# DRIVER_2.net
KiCad netlist of a schematic drawn in Altium Designer
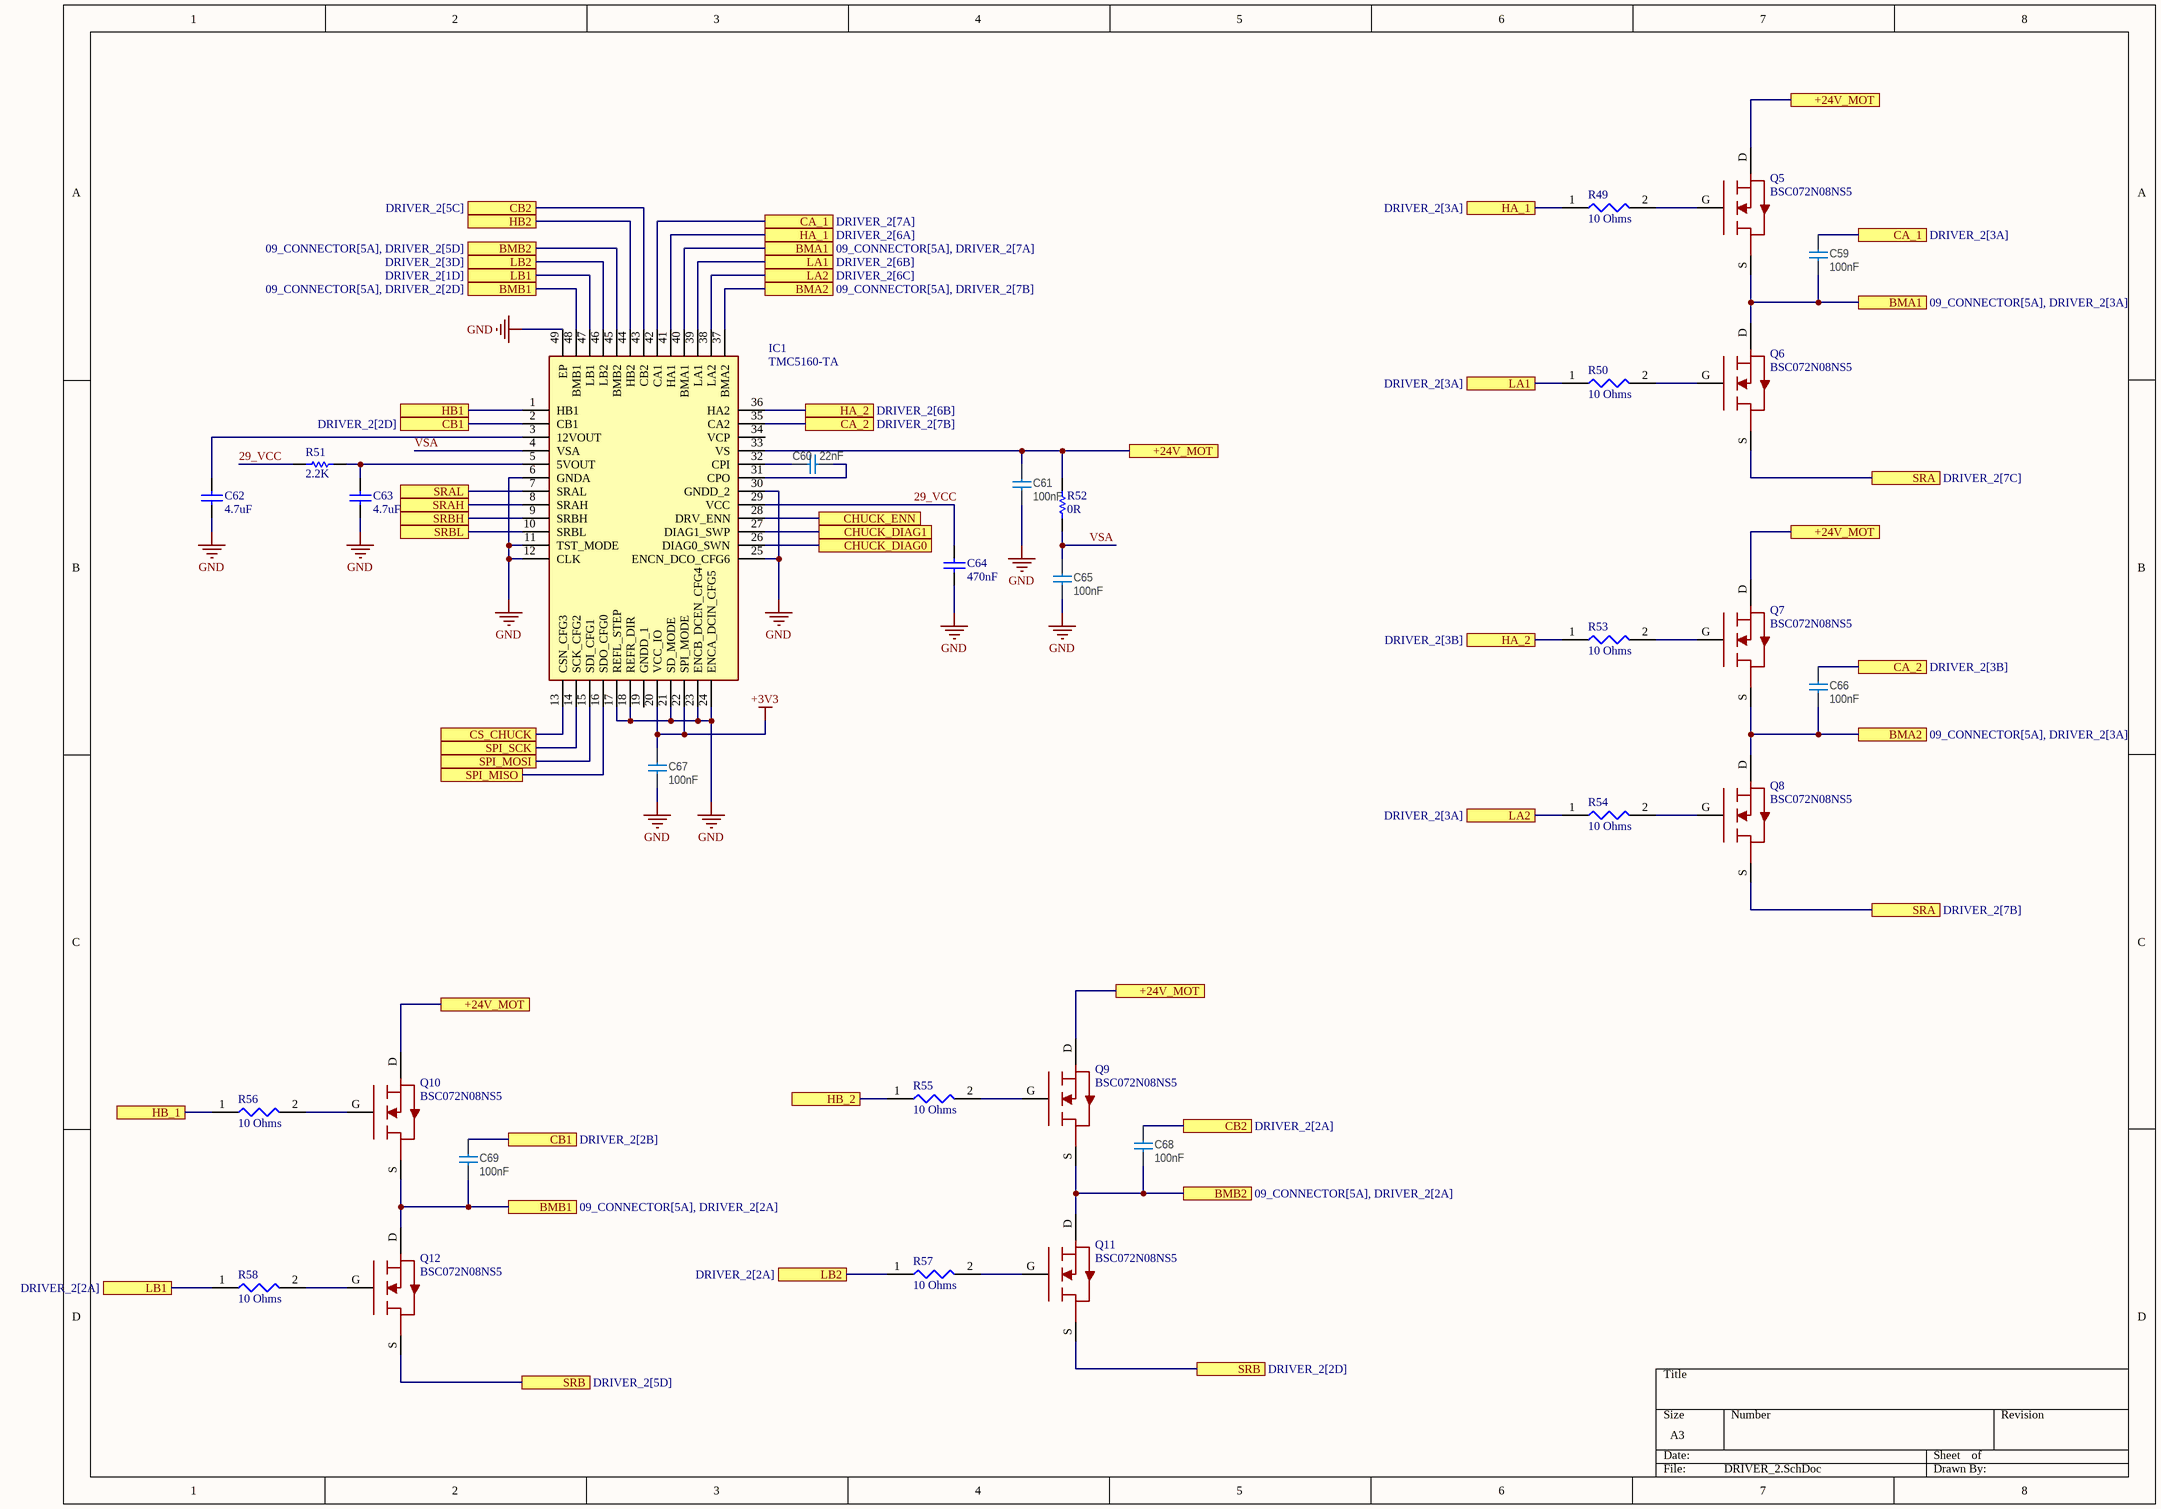
[diagram p0: DRIVER_2.SchDoc]

(export (version "E")
  (design (tool "Eeschema 10.0.6"))
  (components
    (comp (ref "C59")
      (value "100nF")
      (footprint "CAPC0603X03L_C")
      (description "Capacitor, X5R, ±10%")
      (fields
        (field (name "PART NUMBER") "C0201-100n")
        (field (name "MANUFACTURER") "N.A.")
        (field (name "AUTHOR") "rsk")
      )
      (libsource (lib "HW_ADHERENT_SYSCTRL_R1_L1") (part "C0201-100n"))
    )
    (comp (ref "C60")
      (value "22nF")
      (footprint "CAPC0603X03L_C")
      (description "Capacitor, Ceramic, 22nF 10V X5R 0201,±10%")
      (fields
        (field (name "PART NUMBER") "C0201-22n-10V-X5R-GRM033R61A223KE84")
        (field (name "MANUFACTURER") "Murata")
        (field (name "AUTHOR") "prbu")
      )
      (libsource (lib "HW_ADHERENT_SYSCTRL_R1_L1") (part "C0201-22n-10V-X5R-GRM033R61A223KE84_1"))
    )
    (comp (ref "C61")
      (value "100nF")
      (footprint "CAPC0603X03L_C")
      (description "Capacitor, X5R, ±10%")
      (fields
        (field (name "PART NUMBER") "C0201-100n")
        (field (name "MANUFACTURER") "N.A.")
        (field (name "AUTHOR") "rsk")
      )
      (libsource (lib "HW_ADHERENT_SYSCTRL_R1_L1") (part "C0201-100n"))
    )
    (comp (ref "C62")
      (value "4.7uF")
      (footprint "SMC0805")
      (description "4.7 µF ±10% 50V Ceramic Capacitor X5R 0805 (2012 Metric)")
      (fields
        (field (name "MANUFACTURER PART NUMBER") "GRT21BR61H475KE13L")
        (field (name "Comment") "CAP CER 4.7UF 50V X5R 0805")
      )
      (libsource (lib "HW_ADHERENT_SYSCTRL_R1_L2") (part "CAP0805_4.7UF_50V"))
    )
    (comp (ref "C63")
      (value "4.7uF")
      (footprint "SMC0805")
      (description "4.7 µF ±10% 50V Ceramic Capacitor X5R 0805 (2012 Metric)")
      (fields
        (field (name "MANUFACTURER PART NUMBER") "GRT21BR61H475KE13L")
        (field (name "Comment") "CAP CER 4.7UF 50V X5R 0805")
      )
      (libsource (lib "HW_ADHERENT_SYSCTRL_R1_L2") (part "CAP0805_4.7UF_50V"))
    )
    (comp (ref "C64")
      (value "470nF")
      (footprint "CAP0402(1005)x0.5")
      (description "0.47 µF ±10% 10V Ceramic Capacitor X5R 0402 (1005 Metric)")
      (fields
        (field (name "MANUFACTURER PART NUMBER") "CL05A474KP5NNNC")
        (field (name "LCSC PART NUMBER") "C47339")
      )
      (libsource (lib "HW_ADHERENT_SYSCTRL_R1_L2") (part "CAP0402_470NF_10V"))
    )
    (comp (ref "C65")
      (value "100nF")
      (footprint "CAPC0603X03L_C")
      (description "Capacitor, X5R, ±10%")
      (fields
        (field (name "PART NUMBER") "C0201-100n")
        (field (name "MANUFACTURER") "N.A.")
        (field (name "AUTHOR") "rsk")
      )
      (libsource (lib "HW_ADHERENT_SYSCTRL_R1_L1") (part "C0201-100n"))
    )
    (comp (ref "C66")
      (value "100nF")
      (footprint "CAPC0603X03L_C")
      (description "Capacitor, X5R, ±10%")
      (fields
        (field (name "PART NUMBER") "C0201-100n")
        (field (name "MANUFACTURER") "N.A.")
        (field (name "AUTHOR") "rsk")
      )
      (libsource (lib "HW_ADHERENT_SYSCTRL_R1_L1") (part "C0201-100n"))
    )
    (comp (ref "C67")
      (value "100nF")
      (footprint "CAPC0603X03L_C")
      (description "Capacitor, X5R, ±10%")
      (fields
        (field (name "PART NUMBER") "C0201-100n")
        (field (name "MANUFACTURER") "N.A.")
        (field (name "AUTHOR") "rsk")
      )
      (libsource (lib "HW_ADHERENT_SYSCTRL_R1_L1") (part "C0201-100n"))
    )
    (comp (ref "C68")
      (value "100nF")
      (footprint "CAPC0603X03L_C")
      (description "Capacitor, X5R, ±10%")
      (fields
        (field (name "PART NUMBER") "C0201-100n")
        (field (name "MANUFACTURER") "N.A.")
        (field (name "AUTHOR") "rsk")
      )
      (libsource (lib "HW_ADHERENT_SYSCTRL_R1_L1") (part "C0201-100n"))
    )
    (comp (ref "C69")
      (value "100nF")
      (footprint "CAPC0603X03L_C")
      (description "Capacitor, X5R, ±10%")
      (fields
        (field (name "PART NUMBER") "C0201-100n")
        (field (name "MANUFACTURER") "N.A.")
        (field (name "AUTHOR") "rsk")
      )
      (libsource (lib "HW_ADHERENT_SYSCTRL_R1_L1") (part "C0201-100n"))
    )
    (comp (ref "IC1")
      (value "TMC5160-TA")
      (footprint "SamacSys:QFP50P900X900X120-49N")
      (description "Integrated Circuit")
      (libsource (lib "*") (part "TMC5160-TA"))
    )
    (comp (ref "Q5")
      (value "BSC072N08NS5")
      (footprint "SamacSys:BSC080N03LSG")
      (description "Transistor")
      (libsource (lib "SamacSys") (part "BSC072N08NS5"))
    )
    (comp (ref "Q6")
      (value "BSC072N08NS5")
      (footprint "SamacSys:BSC080N03LSG")
      (description "Transistor")
      (libsource (lib "SamacSys") (part "BSC072N08NS5"))
    )
    (comp (ref "Q7")
      (value "BSC072N08NS5")
      (footprint "SamacSys:BSC080N03LSG")
      (description "Transistor")
      (libsource (lib "SamacSys") (part "BSC072N08NS5"))
    )
    (comp (ref "Q8")
      (value "BSC072N08NS5")
      (footprint "SamacSys:BSC080N03LSG")
      (description "Transistor")
      (libsource (lib "SamacSys") (part "BSC072N08NS5"))
    )
    (comp (ref "Q9")
      (value "BSC072N08NS5")
      (footprint "SamacSys:BSC080N03LSG")
      (description "Transistor")
      (libsource (lib "SamacSys") (part "BSC072N08NS5"))
    )
    (comp (ref "Q10")
      (value "BSC072N08NS5")
      (footprint "SamacSys:BSC080N03LSG")
      (description "Transistor")
      (libsource (lib "SamacSys") (part "BSC072N08NS5"))
    )
    (comp (ref "Q11")
      (value "BSC072N08NS5")
      (footprint "SamacSys:BSC080N03LSG")
      (description "Transistor")
      (libsource (lib "SamacSys") (part "BSC072N08NS5"))
    )
    (comp (ref "Q12")
      (value "BSC072N08NS5")
      (footprint "SamacSys:BSC080N03LSG")
      (description "Transistor")
      (libsource (lib "SamacSys") (part "BSC072N08NS5"))
    )
    (comp (ref "R49")
      (value "10 Ohms")
      (footprint "SamacSys:RESC1608X55N")
      (description "Resistor")
      (fields
        (field (name "MANUFACTURER_PART_NUMBER") "RNCF0603AKT10R0")
        (field (name "MOUSER PART NUMBER") "708-RNCF0603AKT10R0")
      )
      (libsource (lib "SamacSys") (part "RNCF0603AKT10R0"))
    )
    (comp (ref "R50")
      (value "10 Ohms")
      (footprint "SamacSys:RESC1608X55N")
      (description "Resistor")
      (fields
        (field (name "MANUFACTURER_PART_NUMBER") "RNCF0603AKT10R0")
        (field (name "MOUSER PART NUMBER") "708-RNCF0603AKT10R0")
      )
      (libsource (lib "SamacSys") (part "RNCF0603AKT10R0"))
    )
    (comp (ref "R51")
      (value "2.2K")
      (footprint "0402_R")
      (description "RES 2.2K OHM 1% 1/16W 0402")
      (fields
        (field (name "MANUFACTURER PART NUMBER") "RC0402FR-072K2L")
        (field (name "MANUFACTURER") "Yageo")
      )
      (libsource (lib "HW_ADHERENT_SYSCTRL_R1_L2") (part "Res1_7"))
    )
    (comp (ref "R52")
      (value "0R")
      (footprint "0402_R")
      (description "RES 0 OHM JUMPER 1/16W 0402")
      (fields
        (field (name "MANUFACTURER PART NUMBER") "RC0402FR-070RL")
        (field (name "MANUFACTURER") "Yageo")
      )
      (libsource (lib "HW_ADHERENT_SYSCTRL_R1_L2") (part "Res1"))
    )
    (comp (ref "R53")
      (value "10 Ohms")
      (footprint "SamacSys:RESC1608X55N")
      (description "Resistor")
      (fields
        (field (name "MANUFACTURER_PART_NUMBER") "RNCF0603AKT10R0")
        (field (name "MOUSER PART NUMBER") "708-RNCF0603AKT10R0")
      )
      (libsource (lib "SamacSys") (part "RNCF0603AKT10R0"))
    )
    (comp (ref "R54")
      (value "10 Ohms")
      (footprint "SamacSys:RESC1608X55N")
      (description "Resistor")
      (fields
        (field (name "MANUFACTURER_PART_NUMBER") "RNCF0603AKT10R0")
        (field (name "MOUSER PART NUMBER") "708-RNCF0603AKT10R0")
      )
      (libsource (lib "SamacSys") (part "RNCF0603AKT10R0"))
    )
    (comp (ref "R55")
      (value "10 Ohms")
      (footprint "SamacSys:RESC1608X55N")
      (description "Resistor")
      (fields
        (field (name "MANUFACTURER_PART_NUMBER") "RNCF0603AKT10R0")
        (field (name "MOUSER PART NUMBER") "708-RNCF0603AKT10R0")
      )
      (libsource (lib "SamacSys") (part "RNCF0603AKT10R0"))
    )
    (comp (ref "R56")
      (value "10 Ohms")
      (footprint "SamacSys:RESC1608X55N")
      (description "Resistor")
      (fields
        (field (name "MANUFACTURER_PART_NUMBER") "RNCF0603AKT10R0")
        (field (name "MOUSER PART NUMBER") "708-RNCF0603AKT10R0")
      )
      (libsource (lib "SamacSys") (part "RNCF0603AKT10R0"))
    )
    (comp (ref "R57")
      (value "10 Ohms")
      (footprint "SamacSys:RESC1608X55N")
      (description "Resistor")
      (fields
        (field (name "MANUFACTURER_PART_NUMBER") "RNCF0603AKT10R0")
        (field (name "MOUSER PART NUMBER") "708-RNCF0603AKT10R0")
      )
      (libsource (lib "SamacSys") (part "RNCF0603AKT10R0"))
    )
    (comp (ref "R58")
      (value "10 Ohms")
      (footprint "SamacSys:RESC1608X55N")
      (description "Resistor")
      (fields
        (field (name "MANUFACTURER_PART_NUMBER") "RNCF0603AKT10R0")
        (field (name "MOUSER PART NUMBER") "708-RNCF0603AKT10R0")
      )
      (libsource (lib "SamacSys") (part "RNCF0603AKT10R0"))
    )
  )
  (nets
    (net (code "1") (name "+3V3") (class "Default")
      (node (ref "C67") (pin "2") (pinfunction "2_2") (pintype "passive"))
      (node (ref "IC1") (pin "20") (pinfunction "VCC_IO_20") (pintype "passive"))
      (node (ref "IC1") (pin "22") (pinfunction "SPI_MODE_22") (pintype "passive"))
    )
    (net (code "2") (name "/+24V_MOT") (class "Default")
      (node (ref "C61") (pin "2") (pinfunction "2_2") (pintype "passive"))
      (node (ref "IC1") (pin "33") (pinfunction "VS_33") (pintype "passive"))
      (node (ref "Q10") (pin "D") (pinfunction "D_D") (pintype "passive"))
      (node (ref "Q5") (pin "D") (pinfunction "D_D") (pintype "passive"))
      (node (ref "Q7") (pin "D") (pinfunction "D_D") (pintype "passive"))
      (node (ref "Q9") (pin "D") (pinfunction "D_D") (pintype "passive"))
      (node (ref "R52") (pin "2") (pinfunction "2_2") (pintype "passive"))
    )
    (net (code "3") (name "/29_VCC") (class "Default")
      (node (ref "C64") (pin "2") (pinfunction "2_2") (pintype "passive"))
      (node (ref "IC1") (pin "29") (pinfunction "VCC_29") (pintype "passive"))
      (node (ref "R51") (pin "2") (pinfunction "2_2") (pintype "passive"))
    )
    (net (code "4") (name "/BMA1") (class "Default")
      (node (ref "C59") (pin "1") (pinfunction "1_1") (pintype "passive"))
      (node (ref "IC1") (pin "40") (pinfunction "BMA1_40") (pintype "passive"))
      (node (ref "Q5") (pin "S") (pinfunction "S_S") (pintype "passive"))
      (node (ref "Q6") (pin "D") (pinfunction "D_D") (pintype "passive"))
    )
    (net (code "5") (name "/BMA2") (class "Default")
      (node (ref "C66") (pin "1") (pinfunction "1_1") (pintype "passive"))
      (node (ref "IC1") (pin "37") (pinfunction "BMA2_37") (pintype "passive"))
      (node (ref "Q7") (pin "S") (pinfunction "S_S") (pintype "passive"))
      (node (ref "Q8") (pin "D") (pinfunction "D_D") (pintype "passive"))
    )
    (net (code "6") (name "/BMB1") (class "Default")
      (node (ref "C69") (pin "1") (pinfunction "1_1") (pintype "passive"))
      (node (ref "IC1") (pin "48") (pinfunction "BMB1_48") (pintype "passive"))
      (node (ref "Q10") (pin "S") (pinfunction "S_S") (pintype "passive"))
      (node (ref "Q12") (pin "D") (pinfunction "D_D") (pintype "passive"))
    )
    (net (code "7") (name "/BMB2") (class "Default")
      (node (ref "C68") (pin "1") (pinfunction "1_1") (pintype "passive"))
      (node (ref "IC1") (pin "45") (pinfunction "BMB2_45") (pintype "passive"))
      (node (ref "Q11") (pin "D") (pinfunction "D_D") (pintype "passive"))
      (node (ref "Q9") (pin "S") (pinfunction "S_S") (pintype "passive"))
    )
    (net (code "8") (name "/CA_1") (class "Default")
      (node (ref "C59") (pin "2") (pinfunction "2_2") (pintype "passive"))
      (node (ref "IC1") (pin "42") (pinfunction "CA1_42") (pintype "passive"))
    )
    (net (code "9") (name "/CA_2") (class "Default")
      (node (ref "C66") (pin "2") (pinfunction "2_2") (pintype "passive"))
      (node (ref "IC1") (pin "35") (pinfunction "CA2_35") (pintype "passive"))
    )
    (net (code "10") (name "/CB1") (class "Default")
      (node (ref "C69") (pin "2") (pinfunction "2_2") (pintype "passive"))
      (node (ref "IC1") (pin "2") (pinfunction "CB1_2") (pintype "passive"))
    )
    (net (code "11") (name "/CB2") (class "Default")
      (node (ref "C68") (pin "2") (pinfunction "2_2") (pintype "passive"))
      (node (ref "IC1") (pin "43") (pinfunction "CB2_43") (pintype "passive"))
    )
    (net (code "12") (name "/CHUCK_DIAG0") (class "Default")
      (node (ref "IC1") (pin "26") (pinfunction "DIAG0_SWN_26") (pintype "passive"))
    )
    (net (code "13") (name "/CHUCK_DIAG1") (class "Default")
      (node (ref "IC1") (pin "27") (pinfunction "DIAG1_SWP_27") (pintype "passive"))
    )
    (net (code "14") (name "/CHUCK_ENN") (class "Default")
      (node (ref "IC1") (pin "28") (pinfunction "DRV_ENN_28") (pintype "passive"))
    )
    (net (code "15") (name "/CS_CHUCK") (class "Default")
      (node (ref "IC1") (pin "13") (pinfunction "CSN_CFG3_13") (pintype "passive"))
    )
    (net (code "16") (name "/HA_1") (class "Default")
      (node (ref "IC1") (pin "41") (pinfunction "HA1_41") (pintype "passive"))
      (node (ref "R49") (pin "1") (pinfunction "1_1") (pintype "passive"))
    )
    (net (code "17") (name "/HA_2") (class "Default")
      (node (ref "IC1") (pin "36") (pinfunction "HA2_36") (pintype "passive"))
      (node (ref "R53") (pin "1") (pinfunction "1_1") (pintype "passive"))
    )
    (net (code "18") (name "/HB1") (class "Default")
      (node (ref "IC1") (pin "1") (pinfunction "HB1_1") (pintype "passive"))
    )
    (net (code "19") (name "/HB2") (class "Default")
      (node (ref "IC1") (pin "44") (pinfunction "HB2_44") (pintype "passive"))
    )
    (net (code "20") (name "/HB_1") (class "Default")
      (node (ref "R56") (pin "1") (pinfunction "1_1") (pintype "passive"))
    )
    (net (code "21") (name "/HB_2") (class "Default")
      (node (ref "R55") (pin "1") (pinfunction "1_1") (pintype "passive"))
    )
    (net (code "22") (name "/LA1") (class "Default")
      (node (ref "IC1") (pin "39") (pinfunction "LA1_39") (pintype "passive"))
      (node (ref "R50") (pin "1") (pinfunction "1_1") (pintype "passive"))
    )
    (net (code "23") (name "/LA2") (class "Default")
      (node (ref "IC1") (pin "38") (pinfunction "LA2_38") (pintype "passive"))
      (node (ref "R54") (pin "1") (pinfunction "1_1") (pintype "passive"))
    )
    (net (code "24") (name "/LB1") (class "Default")
      (node (ref "IC1") (pin "47") (pinfunction "LB1_47") (pintype "passive"))
      (node (ref "R58") (pin "1") (pinfunction "1_1") (pintype "passive"))
    )
    (net (code "25") (name "/LB2") (class "Default")
      (node (ref "IC1") (pin "46") (pinfunction "LB2_46") (pintype "passive"))
      (node (ref "R57") (pin "1") (pinfunction "1_1") (pintype "passive"))
    )
    (net (code "26") (name "/SPI_MISO") (class "Default")
      (node (ref "IC1") (pin "16") (pinfunction "SDO_CFG0_16") (pintype "passive"))
    )
    (net (code "27") (name "/SPI_MOSI") (class "Default")
      (node (ref "IC1") (pin "15") (pinfunction "SDI_CFG1_15") (pintype "passive"))
    )
    (net (code "28") (name "/SPI_SCK") (class "Default")
      (node (ref "IC1") (pin "14") (pinfunction "SCK_CFG2_14") (pintype "passive"))
    )
    (net (code "29") (name "/SRA") (class "Default")
      (node (ref "Q6") (pin "S") (pinfunction "S_S") (pintype "passive"))
      (node (ref "Q8") (pin "S") (pinfunction "S_S") (pintype "passive"))
    )
    (net (code "30") (name "/SRAH") (class "Default")
      (node (ref "IC1") (pin "8") (pinfunction "SRAH_8") (pintype "passive"))
    )
    (net (code "31") (name "/SRAL") (class "Default")
      (node (ref "IC1") (pin "7") (pinfunction "SRAL_7") (pintype "passive"))
    )
    (net (code "32") (name "/SRB") (class "Default")
      (node (ref "Q11") (pin "S") (pinfunction "S_S") (pintype "passive"))
      (node (ref "Q12") (pin "S") (pinfunction "S_S") (pintype "passive"))
    )
    (net (code "33") (name "/SRBH") (class "Default")
      (node (ref "IC1") (pin "9") (pinfunction "SRBH_9") (pintype "passive"))
    )
    (net (code "34") (name "/SRBL") (class "Default")
      (node (ref "IC1") (pin "10") (pinfunction "SRBL_10") (pintype "passive"))
    )
    (net (code "35") (name "/VSA") (class "Default")
      (node (ref "C65") (pin "2") (pinfunction "2_2") (pintype "passive"))
      (node (ref "IC1") (pin "4") (pinfunction "VSA_4") (pintype "passive"))
      (node (ref "R52") (pin "1") (pinfunction "1_1") (pintype "passive"))
    )
    (net (code "36") (name "GND") (class "Default")
      (node (ref "C61") (pin "1") (pinfunction "1_1") (pintype "passive"))
      (node (ref "C62") (pin "1") (pinfunction "1_1") (pintype "passive"))
      (node (ref "C63") (pin "1") (pinfunction "1_1") (pintype "passive"))
      (node (ref "C64") (pin "1") (pinfunction "1_1") (pintype "passive"))
      (node (ref "C65") (pin "1") (pinfunction "1_1") (pintype "passive"))
      (node (ref "C67") (pin "1") (pinfunction "1_1") (pintype "passive"))
      (node (ref "IC1") (pin "11") (pinfunction "TST_MODE_11") (pintype "passive"))
      (node (ref "IC1") (pin "12") (pinfunction "CLK_12") (pintype "passive"))
      (node (ref "IC1") (pin "17") (pinfunction "REFL_STEP_17") (pintype "passive"))
      (node (ref "IC1") (pin "18") (pinfunction "REFR_DIR_18") (pintype "passive"))
      (node (ref "IC1") (pin "21") (pinfunction "SD_MODE_21") (pintype "passive"))
      (node (ref "IC1") (pin "23") (pinfunction "ENCB_DCEN_CFG4_23") (pintype "passive"))
      (node (ref "IC1") (pin "24") (pinfunction "ENCA_DCIN_CFG5_24") (pintype "passive"))
      (node (ref "IC1") (pin "25") (pinfunction "ENCN_DCO_CFG6_25") (pintype "passive"))
      (node (ref "IC1") (pin "30") (pinfunction "GNDD_2_30") (pintype "passive"))
      (node (ref "IC1") (pin "49") (pinfunction "EP_49") (pintype "passive"))
      (node (ref "IC1") (pin "6") (pinfunction "GNDA_6") (pintype "passive"))
    )
    (net (code "37") (name "Net-(IC1-5VOUT)") (class "Default")
      (node (ref "C63") (pin "2") (pinfunction "2_2") (pintype "passive"))
      (node (ref "IC1") (pin "5") (pinfunction "5VOUT_5") (pintype "passive"))
      (node (ref "R51") (pin "1") (pinfunction "1_1") (pintype "passive"))
    )
    (net (code "38") (name "Net-(IC1-12VOUT)") (class "Default")
      (node (ref "C62") (pin "2") (pinfunction "2_2") (pintype "passive"))
      (node (ref "IC1") (pin "3") (pinfunction "12VOUT_3") (pintype "passive"))
    )
    (net (code "39") (name "Net-(IC1-CPI)") (class "Default")
      (node (ref "C60") (pin "1") (pinfunction "1_1") (pintype "passive"))
      (node (ref "IC1") (pin "32") (pinfunction "CPI_32") (pintype "passive"))
    )
    (net (code "40") (name "Net-(IC1-CPO)") (class "Default")
      (node (ref "C60") (pin "2") (pinfunction "2_2") (pintype "passive"))
      (node (ref "IC1") (pin "31") (pinfunction "CPO_31") (pintype "passive"))
    )
    (net (code "41") (name "Net-(Q5-PadG)") (class "Default")
      (node (ref "Q5") (pin "G") (pinfunction "G_G") (pintype "passive"))
      (node (ref "R49") (pin "2") (pinfunction "2_2") (pintype "passive"))
    )
    (net (code "42") (name "Net-(Q6-PadG)") (class "Default")
      (node (ref "Q6") (pin "G") (pinfunction "G_G") (pintype "passive"))
      (node (ref "R50") (pin "2") (pinfunction "2_2") (pintype "passive"))
    )
    (net (code "43") (name "Net-(Q7-PadG)") (class "Default")
      (node (ref "Q7") (pin "G") (pinfunction "G_G") (pintype "passive"))
      (node (ref "R53") (pin "2") (pinfunction "2_2") (pintype "passive"))
    )
    (net (code "44") (name "Net-(Q8-PadG)") (class "Default")
      (node (ref "Q8") (pin "G") (pinfunction "G_G") (pintype "passive"))
      (node (ref "R54") (pin "2") (pinfunction "2_2") (pintype "passive"))
    )
    (net (code "45") (name "Net-(Q9-PadG)") (class "Default")
      (node (ref "Q9") (pin "G") (pinfunction "G_G") (pintype "passive"))
      (node (ref "R55") (pin "2") (pinfunction "2_2") (pintype "passive"))
    )
    (net (code "46") (name "Net-(Q10-PadG)") (class "Default")
      (node (ref "Q10") (pin "G") (pinfunction "G_G") (pintype "passive"))
      (node (ref "R56") (pin "2") (pinfunction "2_2") (pintype "passive"))
    )
    (net (code "47") (name "Net-(Q11-PadG)") (class "Default")
      (node (ref "Q11") (pin "G") (pinfunction "G_G") (pintype "passive"))
      (node (ref "R57") (pin "2") (pinfunction "2_2") (pintype "passive"))
    )
    (net (code "48") (name "Net-(Q12-PadG)") (class "Default")
      (node (ref "Q12") (pin "G") (pinfunction "G_G") (pintype "passive"))
      (node (ref "R58") (pin "2") (pinfunction "2_2") (pintype "passive"))
    )
    (net (code "49") (name "unconnected-(IC1-GNDD_1-Pad19)") (class "Default")
      (node (ref "IC1") (pin "19") (pinfunction "GNDD_1_19") (pintype "passive"))
    )
    (net (code "50") (name "unconnected-(IC1-VCP-Pad34)") (class "Default")
      (node (ref "IC1") (pin "34") (pinfunction "VCP_34") (pintype "passive"))
    )
  )
)
